# ARM_PCB.net
KiCad netlist of a schematic drawn in Altium Designer
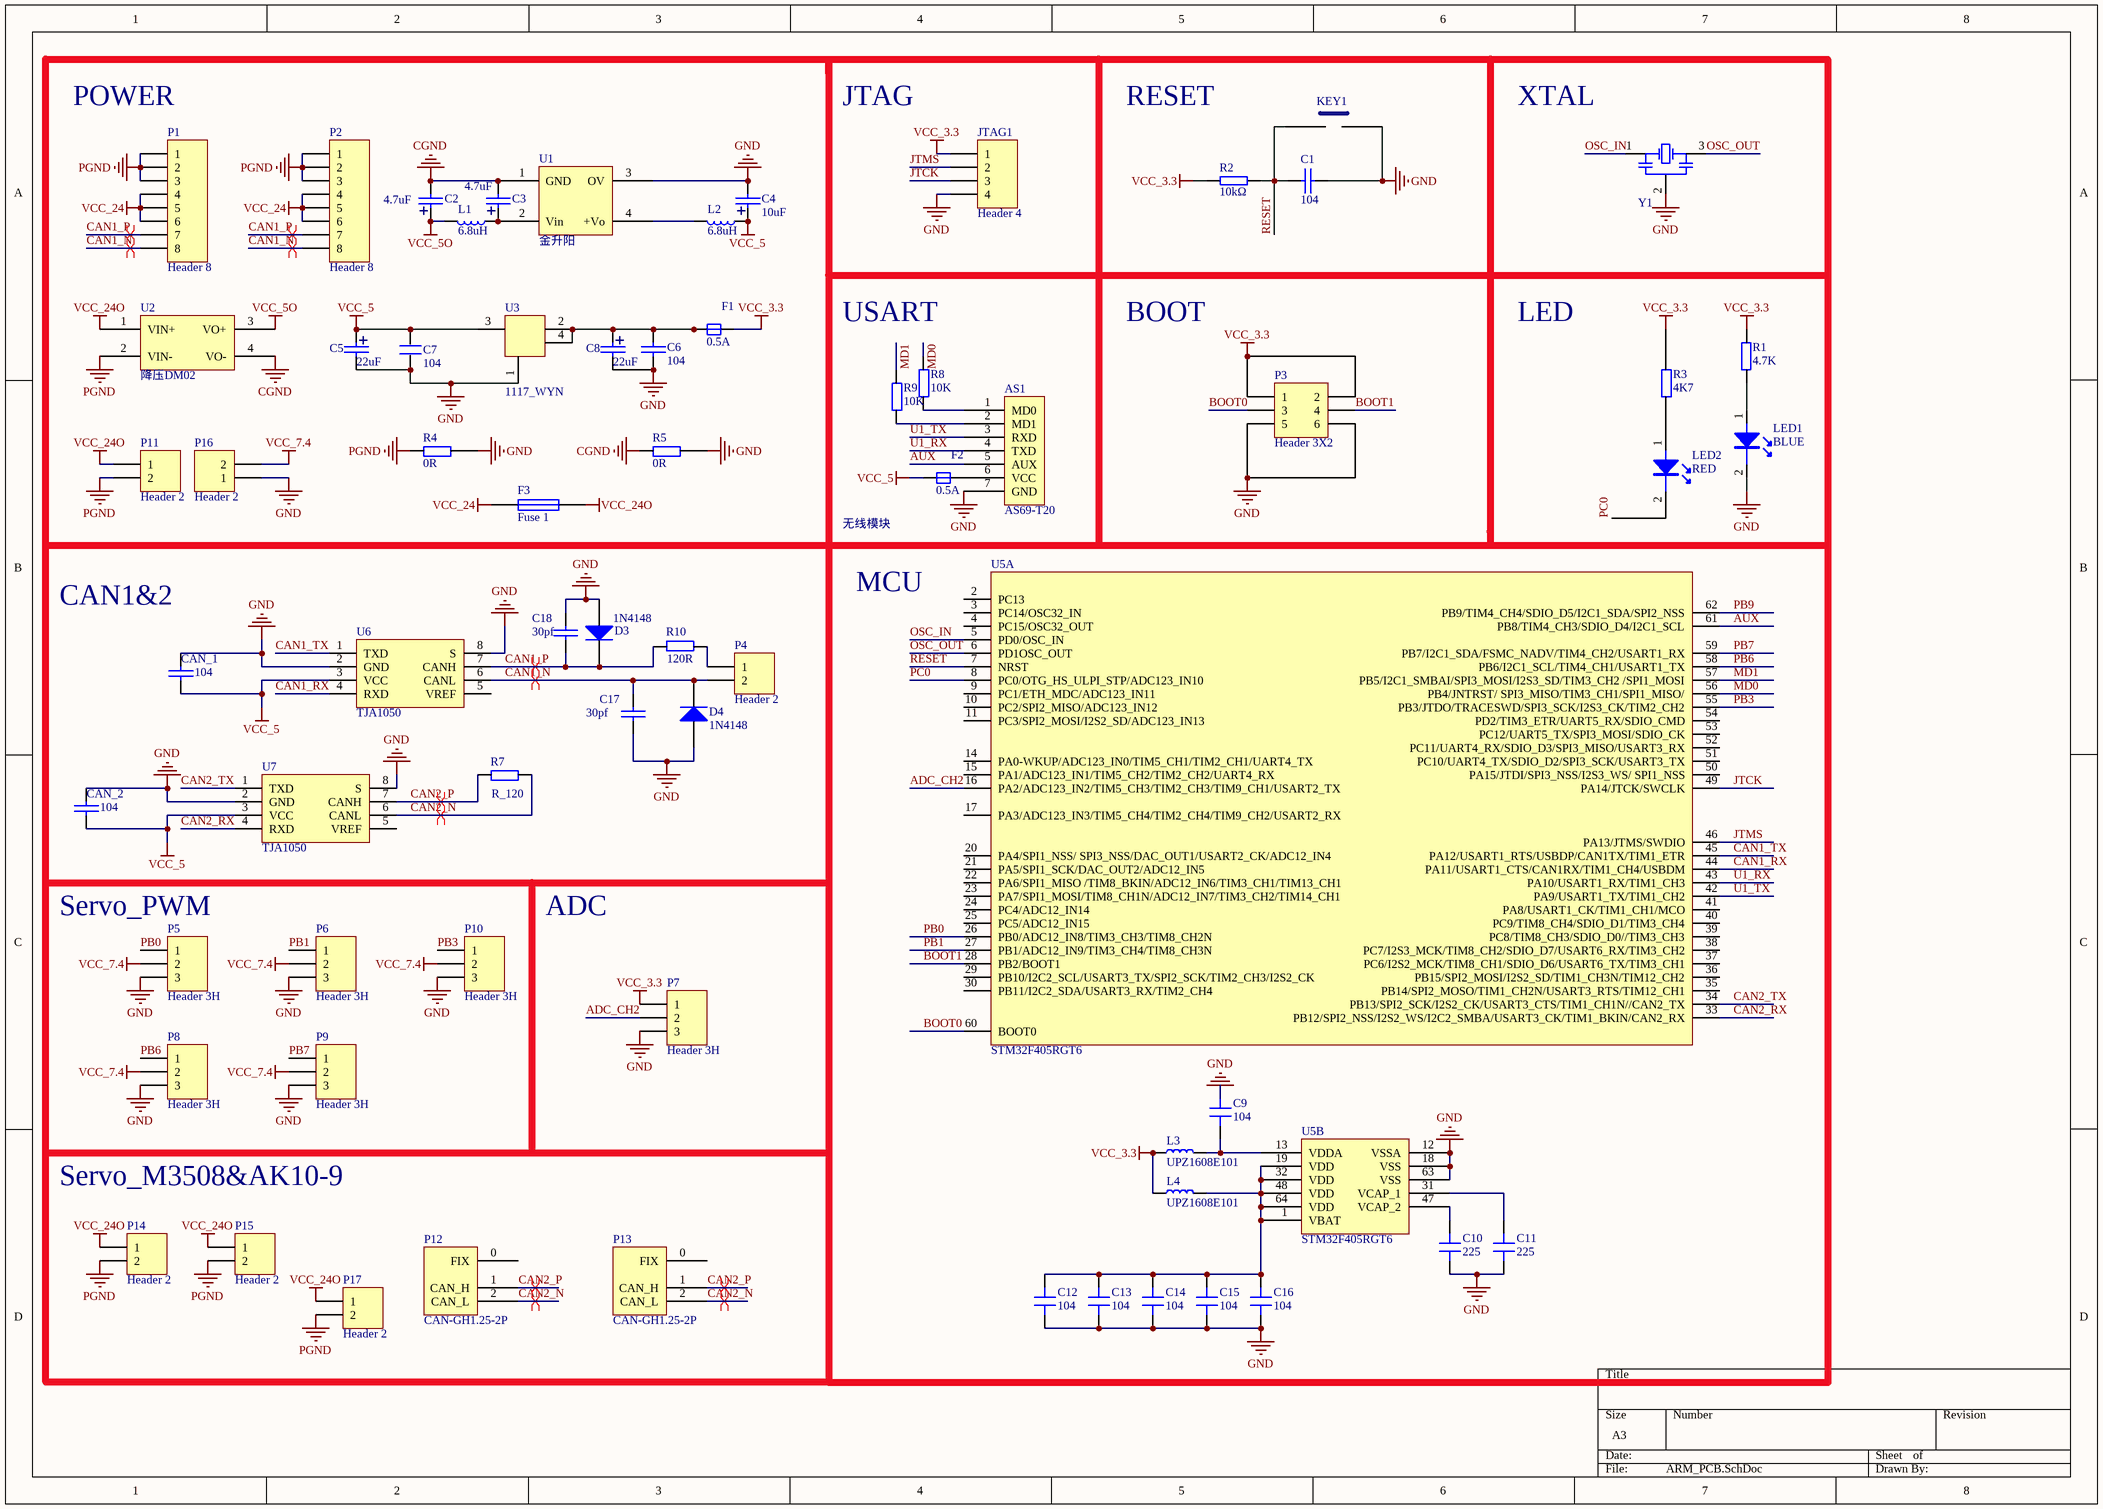
[diagram p0: ARM_PCB.SchDoc]

(export (version "E")
  (design (tool "Eeschema 10.0.6"))
  (components
    (comp (ref "AS1")
      (value "AS69-T20")
      (footprint "HDR2.54-M-LI-7P")
      (libsource (lib "PCB_Project") (part "AS69-T20"))
    )
    (comp (ref "C1") (value "104") (footprint "C0603") (libsource (lib "main") (part "C0603")))
    (comp (ref "C2")
      (value "4.7uF")
      (footprint "A3216")
      (libsource (lib "PCB_PROJECT1") (part "CAP_POL_WYN"))
    )
    (comp (ref "C3")
      (value "4.7uF")
      (footprint "A3216")
      (libsource (lib "PCB_PROJECT1") (part "CAP_POL_WYN"))
    )
    (comp (ref "C4") (value "10uF") (footprint "A3216") (libsource (lib "PCB_PROJECT1") (part "CAP_POL_WYN")))
    (comp (ref "C5") (value "22uF") (footprint "A3216") (libsource (lib "PCB_PROJECT1") (part "CAP_POL_WYN")))
    (comp (ref "C6") (value "104") (footprint "C0603") (libsource (lib "main") (part "C0603")))
    (comp (ref "C7") (value "104") (footprint "C0603") (libsource (lib "Rescue") (part "Cap")))
    (comp (ref "C8") (value "22uF") (footprint "A3216") (libsource (lib "PCB_PROJECT1") (part "CAP_POL_WYN")))
    (comp (ref "C9")
      (value "104")
      (footprint "C0603/1608")
      (description "陶瓷电容")
      (libsource (lib "WMJ2019_Devices") (part "陶瓷电容"))
    )
    (comp (ref "C10")
      (value "225")
      (footprint "C0603/1608")
      (description "陶瓷电容")
      (libsource (lib "WMJ2019_Devices") (part "陶瓷电容"))
    )
    (comp (ref "C11")
      (value "225")
      (footprint "C0603/1608")
      (description "陶瓷电容")
      (libsource (lib "WMJ2019_Devices") (part "陶瓷电容"))
    )
    (comp (ref "C12")
      (value "104")
      (footprint "C0603/1608")
      (description "陶瓷电容")
      (libsource (lib "WMJ2019_Devices") (part "陶瓷电容"))
    )
    (comp (ref "C13")
      (value "104")
      (footprint "C0603/1608")
      (description "陶瓷电容")
      (libsource (lib "WMJ2019_Devices") (part "陶瓷电容"))
    )
    (comp (ref "C14")
      (value "104")
      (footprint "C0603/1608")
      (description "陶瓷电容")
      (libsource (lib "WMJ2019_Devices") (part "陶瓷电容"))
    )
    (comp (ref "C15")
      (value "104")
      (footprint "C0603/1608")
      (description "陶瓷电容")
      (libsource (lib "WMJ2019_Devices") (part "陶瓷电容"))
    )
    (comp (ref "C16")
      (value "104")
      (footprint "C0603/1608")
      (description "陶瓷电容")
      (libsource (lib "WMJ2019_Devices") (part "陶瓷电容"))
    )
    (comp (ref "C17") (value "30pf") (footprint "C0603") (libsource (lib "PCB_Project") (part "CAP_WYN")))
    (comp (ref "C18") (value "30pf") (footprint "C0603") (libsource (lib "PCB_Project") (part "CAP_WYN")))
    (comp (ref "CAN_1") (value "104") (footprint "C0603") (libsource (lib "STM32主处理板") (part "C0603")))
    (comp (ref "CAN_2") (value "104") (footprint "C0603") (libsource (lib "STM32主处理板") (part "C0603")))
    (comp (ref "D3")
      (value "1N4148")
      (footprint "MINI_MELF (LL34)")
      (description "Default Diode")
      (fields (field (name "PUBLISHER") "Altium Limited"))
      (libsource (lib "Miscellaneous Devices") (part "Diode"))
    )
    (comp (ref "D4")
      (value "1N4148")
      (footprint "MINI_MELF (LL34)")
      (description "Default Diode")
      (fields (field (name "PUBLISHER") "Altium Limited"))
      (libsource (lib "Miscellaneous Devices") (part "Diode"))
    )
    (comp (ref "F1") (value "0.5A") (footprint "L0603") (libsource (lib "舞蹈常用原理图库") (part "FUSE")))
    (comp (ref "F2") (value "0.5A") (footprint "L0603") (libsource (lib "舞蹈常用原理图库") (part "FUSE")))
    (comp (ref "F3")
      (value "Fuse 1")
      (footprint "Fuse")
      (description "Fuse")
      (fields (field (name "PUBLISHER") "Altium Limited"))
      (libsource (lib "Miscellaneous Devices") (part "Fuse 1"))
    )
    (comp (ref "JTAG1")
      (value "Header 4")
      (footprint "Header1*4_XH2.54_zhi")
      (description "Header, 4-Pin")
      (fields (field (name "PUBLISHER") "Altium Limited"))
      (libsource (lib "Miscellaneous Connectors") (part "Header 4"))
    )
    (comp (ref "KEY1") (value "KEY2") (footprint "KEY_RESET") (libsource (lib "library-1") (part "KEY")))
    (comp (ref "L1")
      (value "6.8uH")
      (footprint "L0630")
      (description "贴片磁珠")
      (libsource (lib "PCB_Project") (part "磁珠"))
    )
    (comp (ref "L2")
      (value "6.8uH")
      (footprint "L0630")
      (description "贴片磁珠")
      (libsource (lib "PCB_Project") (part "磁珠"))
    )
    (comp (ref "L3")
      (value "UPZ1608E101")
      (footprint "L0603/1608")
      (description "贴片磁珠")
      (libsource (lib "WMJ2019_Devices") (part "磁珠"))
    )
    (comp (ref "L4")
      (value "UPZ1608E101")
      (footprint "L0603/1608")
      (description "贴片磁珠")
      (libsource (lib "WMJ2019_Devices") (part "磁珠"))
    )
    (comp (ref "LED1")
      (value "LED BLUE")
      (footprint "LED0603")
      (fields (field (name "COLOR") "BLUE"))
      (libsource (lib "Rescue") (part "LED"))
    )
    (comp (ref "LED2")
      (value "LED RED")
      (footprint "LED0603")
      (fields (field (name "COLOR") "RED"))
      (libsource (lib "Rescue") (part "LED"))
    )
    (comp (ref "P1")
      (value "Header 8")
      (footprint "XH2.54-WI-8P")
      (description "Header, 8-Pin")
      (fields (field (name "PUBLISHER") "Altium Limited"))
      (libsource (lib "Miscellaneous Connectors") (part "Header 8"))
    )
    (comp (ref "P2")
      (value "Header 8")
      (footprint "Header1*8_XH2.54_zhi")
      (description "Header, 8-Pin")
      (fields (field (name "PUBLISHER") "Altium Limited"))
      (libsource (lib "Miscellaneous Connectors") (part "Header 8"))
    )
    (comp (ref "P3")
      (value "Header 3X2")
      (footprint "BOOT")
      (description "Header, 3-Pin, Dual row")
      (fields (field (name "PUBLISHER") "Altium Limited"))
      (libsource (lib "PCB_Project") (part "Header 3X2"))
    )
    (comp (ref "P4") (value "Header 2") (footprint "TM") (libsource (lib "") (part "Header 2_1")))
    (comp (ref "P5")
      (value "Header 3H")
      (footprint "XH2.54-WI-3P")
      (libsource (lib "Rescue") (part "Header 3H"))
    )
    (comp (ref "P6")
      (value "Header 3H")
      (footprint "XH2.54-WI-3P")
      (libsource (lib "Rescue") (part "Header 3H"))
    )
    (comp (ref "P7")
      (value "Header 3H")
      (footprint "XH2.54-WI-3P")
      (libsource (lib "Rescue") (part "Header 3H"))
    )
    (comp (ref "P8")
      (value "Header 3H")
      (footprint "XH2.54-WI-3P")
      (libsource (lib "Rescue") (part "Header 3H"))
    )
    (comp (ref "P9")
      (value "Header 3H")
      (footprint "XH2.54-WI-3P")
      (libsource (lib "Rescue") (part "Header 3H"))
    )
    (comp (ref "P10")
      (value "Header 3H")
      (footprint "XH2.54-WI-3P")
      (libsource (lib "Rescue") (part "Header 3H"))
    )
    (comp (ref "P11") (value "Header 2") (footprint "KF301-5.0-2P") (libsource (lib "") (part "Header 2_1")))
    (comp (ref "P12")
      (value "CAN-GH1.25-2P")
      (footprint "XH2.54-LI-2P")
      (description "CAN-GH1.25-2P端子座")
      (libsource (lib "PCB_Project1") (part "CAN-GH1.25-2P"))
    )
    (comp (ref "P13")
      (value "CAN-GH1.25-2P")
      (footprint "XH2.54-LI-2P")
      (description "CAN-GH1.25-2P端子座")
      (libsource (lib "PCB_Project1") (part "CAN-GH1.25-2P"))
    )
    (comp (ref "P14") (value "Header 2") (footprint "xt30公头（立式）") (libsource (lib "") (part "Header 2_1")))
    (comp (ref "P15") (value "Header 2") (footprint "xt30公头（立式）") (libsource (lib "") (part "Header 2_1")))
    (comp (ref "P16")
      (value "Header 2")
      (footprint "KF301-5.0-2P")
      (libsource (lib "Rescue") (part "Header 2"))
    )
    (comp (ref "P17") (value "Header 2") (footprint "XT30_母") (libsource (lib "") (part "Header 2_1")))
    (comp (ref "R1") (value "4.7K") (footprint "R0603") (libsource (lib "战舰STM32开发板底板封装库") (part "R")))
    (comp (ref "R2") (value "10kΩ") (footprint "R0603") (libsource (lib "main") (part "RES_WYN")))
    (comp (ref "R3") (value "4K7") (footprint "R0603") (libsource (lib "Rescue") (part "Resistor")))
    (comp (ref "R4") (value "0R") (footprint "R0603") (libsource (lib "Rescue") (part "Resistor")))
    (comp (ref "R5") (value "0R") (footprint "R0603") (libsource (lib "Rescue") (part "Resistor")))
    (comp (ref "R7") (value "R_120") (footprint "R0603") (libsource (lib "战舰STM32开发板底板封装库") (part "R")))
    (comp (ref "R8") (value "10K") (footprint "R0603") (libsource (lib "PCB_Project") (part "Resistor")))
    (comp (ref "R9") (value "10K") (footprint "R0603") (libsource (lib "PCB_Project") (part "Resistor")))
    (comp (ref "R10") (value "120R") (footprint "R0603") (libsource (lib "PCB_Project") (part "Resistor")))
    (comp (ref "U1") (value "金升阳") (footprint "金升阳") (libsource (lib "RESCUE2019") (part "金升阳")))
    (comp (ref "U2") (value "降压DM02") (footprint "降压DM02") (libsource (lib "Rescue") (part "降压DM02")))
    (comp (ref "U3") (value "1117_WYN") (footprint "SOT-223") (libsource (lib "STM32主处理板") (part "1117_WYN")))
    (comp (ref "U5")
      (value "STM32F405RGT6")
      (footprint "LQFP64")
      (description "微控制器STM32F405RGT6")
      (libsource (lib "WMJ2019_MCU") (part "STM32F405RGT6"))
    )
    (comp (ref "U6") (value "TJA1050") (footprint "SO8_M") (libsource (lib "Rescue") (part "TJA1050")))
    (comp (ref "U7") (value "TJA1050") (footprint "SO8_M") (libsource (lib "Rescue") (part "TJA1050")))
    (comp (ref "Y1")
      (value "Crystal_Cap")
      (footprint "XTAL-3213")
      (fields (field (name "PUBLISHER") "Altium Limited"))
      (libsource (lib "chassis_PCB_Project") (part "Crystal_Cap"))
    )
  )
  (nets
    (net (code "1") (name "/ADC_CH2") (class "Default")
      (node (ref "P7") (pin "2") (pinfunction "2_2") (pintype "passive"))
      (node (ref "U5") (pin "16") (pinfunction "PA2/ADC123_IN2/TIM5_CH3/TIM2_CH3/TIM9_CH1/USART2_TX_16") (pintype "passive"))
    )
    (net (code "2") (name "/AUX") (class "Default")
      (node (ref "AS1") (pin "5") (pinfunction "AUX_5") (pintype "passive"))
      (node (ref "U5") (pin "61") (pinfunction "PB8/TIM4_CH3/SDIO_D4/I2C1_SCL_61") (pintype "passive"))
    )
    (net (code "3") (name "/BOOT0") (class "Default")
      (node (ref "P3") (pin "3") (pinfunction "3_3") (pintype "passive"))
      (node (ref "U5") (pin "60") (pinfunction "BOOT0_60") (pintype "passive"))
    )
    (net (code "4") (name "/BOOT1") (class "Default")
      (node (ref "P3") (pin "4") (pinfunction "4_4") (pintype "passive"))
      (node (ref "U5") (pin "28") (pinfunction "PB2/BOOT1_28") (pintype "passive"))
    )
    (net (code "5") (name "/CAN1_N") (class "Default")
      (node (ref "C17") (pin "1") (pintype "passive"))
      (node (ref "D4") (pin "2") (pinfunction "K_2") (pintype "passive"))
      (node (ref "P1") (pin "8") (pinfunction "8_8") (pintype "passive"))
      (node (ref "P2") (pin "8") (pinfunction "8_8") (pintype "passive"))
      (node (ref "P4") (pin "2") (pinfunction "2_2") (pintype "passive"))
      (node (ref "U6") (pin "6") (pinfunction "CANL_6") (pintype "passive"))
    )
    (net (code "6") (name "/CAN1_P") (class "Default")
      (node (ref "C18") (pin "2") (pintype "passive"))
      (node (ref "D3") (pin "2") (pinfunction "K_2") (pintype "passive"))
      (node (ref "P1") (pin "7") (pinfunction "7_7") (pintype "passive"))
      (node (ref "P2") (pin "7") (pinfunction "7_7") (pintype "passive"))
      (node (ref "R10") (pin "2") (pintype "passive"))
      (node (ref "U6") (pin "7") (pinfunction "CANH_7") (pintype "passive"))
    )
    (net (code "7") (name "/CAN1_RX") (class "Default")
      (node (ref "U5") (pin "44") (pinfunction "PA11/USART1_CTS/CAN1RX/TIM1_CH4/USBDM_44") (pintype "passive"))
      (node (ref "U6") (pin "4") (pinfunction "RXD_4") (pintype "passive"))
    )
    (net (code "8") (name "/CAN1_TX") (class "Default")
      (node (ref "U5") (pin "45") (pinfunction "PA12/USART1_RTS/USBDP/CAN1TX/TIM1_ETR_45") (pintype "passive"))
      (node (ref "U6") (pin "1") (pinfunction "TXD_1") (pintype "passive"))
    )
    (net (code "9") (name "/CAN2_N") (class "Default")
      (node (ref "P12") (pin "2") (pinfunction "CAN_L_2") (pintype "passive"))
      (node (ref "P13") (pin "2") (pinfunction "CAN_L_2") (pintype "passive"))
      (node (ref "R7") (pin "2") (pintype "passive"))
      (node (ref "U7") (pin "6") (pinfunction "CANL_6") (pintype "passive"))
    )
    (net (code "10") (name "/CAN2_P") (class "Default")
      (node (ref "P12") (pin "1") (pinfunction "CAN_H_1") (pintype "passive"))
      (node (ref "P13") (pin "1") (pinfunction "CAN_H_1") (pintype "passive"))
      (node (ref "R7") (pin "1") (pintype "passive"))
      (node (ref "U7") (pin "7") (pinfunction "CANH_7") (pintype "passive"))
    )
    (net (code "11") (name "/CAN2_RX") (class "Default")
      (node (ref "U5") (pin "33") (pinfunction "PB12/SPI2_NSS/I2S2_WS/I2C2_SMBA/USART3_CK/TIM1_BKIN/CAN2_RX_33") (pintype "passive"))
      (node (ref "U7") (pin "4") (pinfunction "RXD_4") (pintype "passive"))
    )
    (net (code "12") (name "/CAN2_TX") (class "Default")
      (node (ref "U5") (pin "34") (pinfunction "PB13/SPI2_SCK/I2S2_CK/USART3_CTS/TIM1_CH1N//CAN2_TX_34") (pintype "passive"))
      (node (ref "U7") (pin "1") (pinfunction "TXD_1") (pintype "passive"))
    )
    (net (code "13") (name "/JTCK") (class "Default")
      (node (ref "JTAG1") (pin "3") (pinfunction "3_3") (pintype "passive"))
      (node (ref "U5") (pin "49") (pinfunction "PA14/JTCK/SWCLK_49") (pintype "passive"))
    )
    (net (code "14") (name "/JTMS") (class "Default")
      (node (ref "JTAG1") (pin "2") (pinfunction "2_2") (pintype "passive"))
      (node (ref "U5") (pin "46") (pinfunction "PA13/JTMS/SWDIO_46") (pintype "passive"))
    )
    (net (code "15") (name "/MD0") (class "Default")
      (node (ref "R8") (pin "2") (pintype "passive"))
      (node (ref "U5") (pin "56") (pinfunction "PB4/JNTRST/_SPI3_MISO/TIM3_CH1/SPI1_MISO/_56") (pintype "passive"))
    )
    (net (code "16") (name "/MD1") (class "Default")
      (node (ref "R9") (pin "2") (pintype "passive"))
      (node (ref "U5") (pin "57") (pinfunction "PB5/I2C1_SMBAI/SPI3_MOSI/I2S3_SD/TIM3_CH2_/SPI1_MOSI_57") (pintype "passive"))
    )
    (net (code "17") (name "/OSC_IN") (class "Default")
      (node (ref "U5") (pin "5") (pinfunction "PD0/OSC_IN_5") (pintype "passive"))
      (node (ref "Y1") (pin "1") (pinfunction "OSC1_1") (pintype "passive"))
    )
    (net (code "18") (name "/OSC_OUT") (class "Default")
      (node (ref "U5") (pin "6") (pinfunction "PD1OSC_OUT_6") (pintype "passive"))
      (node (ref "Y1") (pin "3") (pinfunction "OSC3_3") (pintype "passive"))
    )
    (net (code "19") (name "/PB0") (class "Default")
      (node (ref "P5") (pin "1") (pinfunction "1_1") (pintype "passive"))
      (node (ref "U5") (pin "26") (pinfunction "PB0/ADC12_IN8/TIM3_CH3/TIM8_CH2N_26") (pintype "passive"))
    )
    (net (code "20") (name "/PB1") (class "Default")
      (node (ref "P6") (pin "1") (pinfunction "1_1") (pintype "passive"))
      (node (ref "U5") (pin "27") (pinfunction "PB1/ADC12_IN9/TIM3_CH4/TIM8_CH3N_27") (pintype "passive"))
    )
    (net (code "21") (name "/PB3") (class "Default")
      (node (ref "P10") (pin "1") (pinfunction "1_1") (pintype "passive"))
      (node (ref "U5") (pin "55") (pinfunction "PB3/JTDO/TRACESWD/SPI3_SCK/I2S3_CK/TIM2_CH2_55") (pintype "passive"))
    )
    (net (code "22") (name "/PB6") (class "Default")
      (node (ref "P8") (pin "1") (pinfunction "1_1") (pintype "passive"))
      (node (ref "U5") (pin "58") (pinfunction "PB6/I2C1_SCL/TIM4_CH1/USART1_TX_58") (pintype "passive"))
    )
    (net (code "23") (name "/PB7") (class "Default")
      (node (ref "P9") (pin "1") (pinfunction "1_1") (pintype "passive"))
      (node (ref "U5") (pin "59") (pinfunction "PB7/I2C1_SDA/FSMC_NADV/TIM4_CH2/USART1_RX_59") (pintype "passive"))
    )
    (net (code "24") (name "/PB9") (class "Default")
      (node (ref "U5") (pin "62") (pinfunction "PB9/TIM4_CH4/SDIO_D5/I2C1_SDA/SPI2_NSS_62") (pintype "passive"))
    )
    (net (code "25") (name "/PC0") (class "Default")
      (node (ref "LED2") (pin "2") (pinfunction "K_2") (pintype "passive"))
      (node (ref "U5") (pin "8") (pinfunction "PC0/OTG_HS_ULPI_STP/ADC123_IN10_8") (pintype "passive"))
    )
    (net (code "26") (name "/RESET") (class "Default")
      (node (ref "C1") (pin "1") (pintype "passive"))
      (node (ref "KEY1") (pin "2") (pinfunction "2_2") (pintype "passive"))
      (node (ref "R2") (pin "1") (pinfunction "1_1") (pintype "passive"))
      (node (ref "U5") (pin "7") (pinfunction "NRST_7") (pintype "passive"))
    )
    (net (code "27") (name "/U1_RX") (class "Default")
      (node (ref "AS1") (pin "4") (pinfunction "TXD_4") (pintype "passive"))
      (node (ref "U5") (pin "43") (pinfunction "PA10/USART1_RX/TIM1_CH3_43") (pintype "passive"))
    )
    (net (code "28") (name "/U1_TX") (class "Default")
      (node (ref "AS1") (pin "3") (pinfunction "RXD_3") (pintype "passive"))
      (node (ref "U5") (pin "42") (pinfunction "PA9/USART1_TX/TIM1_CH2_42") (pintype "passive"))
    )
    (net (code "29") (name "CGND") (class "Default")
      (node (ref "C2") (pin "2") (pintype "passive"))
      (node (ref "C3") (pin "2") (pintype "passive"))
      (node (ref "R5") (pin "1") (pintype "passive"))
      (node (ref "U1") (pin "1") (pinfunction "GND_1") (pintype "passive"))
      (node (ref "U2") (pin "4") (pinfunction "VO-_4") (pintype "passive"))
    )
    (net (code "30") (name "GND") (class "Default")
      (node (ref "AS1") (pin "7") (pinfunction "GND_7") (pintype "passive"))
      (node (ref "C1") (pin "2") (pintype "passive"))
      (node (ref "C10") (pin "1") (pintype "passive"))
      (node (ref "C11") (pin "1") (pintype "passive"))
      (node (ref "C12") (pin "1") (pintype "passive"))
      (node (ref "C13") (pin "1") (pintype "passive"))
      (node (ref "C14") (pin "1") (pintype "passive"))
      (node (ref "C15") (pin "1") (pintype "passive"))
      (node (ref "C16") (pin "1") (pintype "passive"))
      (node (ref "C17") (pin "2") (pintype "passive"))
      (node (ref "C18") (pin "1") (pintype "passive"))
      (node (ref "C4") (pin "2") (pintype "passive"))
      (node (ref "C5") (pin "2") (pintype "passive"))
      (node (ref "C6") (pin "2") (pintype "passive"))
      (node (ref "C7") (pin "1") (pintype "passive"))
      (node (ref "C8") (pin "2") (pintype "passive"))
      (node (ref "C9") (pin "2") (pintype "passive"))
      (node (ref "CAN_1") (pin "1") (pintype "passive"))
      (node (ref "CAN_2") (pin "1") (pintype "passive"))
      (node (ref "D3") (pin "1") (pinfunction "A_1") (pintype "passive"))
      (node (ref "D4") (pin "1") (pinfunction "A_1") (pintype "passive"))
      (node (ref "JTAG1") (pin "4") (pinfunction "4_4") (pintype "passive"))
      (node (ref "KEY1") (pin "1") (pinfunction "1_1") (pintype "passive"))
      (node (ref "LED1") (pin "2") (pinfunction "K_2") (pintype "passive"))
      (node (ref "P10") (pin "3") (pinfunction "3_3") (pintype "passive"))
      (node (ref "P16") (pin "1") (pinfunction "1_1") (pintype "passive"))
      (node (ref "P3") (pin "5") (pinfunction "5_5") (pintype "passive"))
      (node (ref "P3") (pin "6") (pinfunction "6_6") (pintype "passive"))
      (node (ref "P5") (pin "3") (pinfunction "3_3") (pintype "passive"))
      (node (ref "P6") (pin "3") (pinfunction "3_3") (pintype "passive"))
      (node (ref "P7") (pin "3") (pinfunction "3_3") (pintype "passive"))
      (node (ref "P8") (pin "3") (pinfunction "3_3") (pintype "passive"))
      (node (ref "P9") (pin "3") (pinfunction "3_3") (pintype "passive"))
      (node (ref "R4") (pin "2") (pintype "passive"))
      (node (ref "R5") (pin "2") (pintype "passive"))
      (node (ref "U1") (pin "3") (pinfunction "OV_3") (pintype "passive"))
      (node (ref "U3") (pin "1") (pintype "passive"))
      (node (ref "U5") (pin "12") (pinfunction "VSSA_12") (pintype "passive"))
      (node (ref "U5") (pin "18") (pinfunction "VSS_18") (pintype "passive"))
      (node (ref "U5") (pin "63") (pinfunction "VSS_63") (pintype "passive"))
      (node (ref "U6") (pin "2") (pinfunction "GND_2") (pintype "passive"))
      (node (ref "U6") (pin "8") (pinfunction "S_8") (pintype "passive"))
      (node (ref "U7") (pin "2") (pinfunction "GND_2") (pintype "passive"))
      (node (ref "U7") (pin "8") (pinfunction "S_8") (pintype "passive"))
      (node (ref "Y1") (pin "2") (pinfunction "OSC2_2") (pintype "passive"))
    )
    (net (code "31") (name "Net-(AS1-MD0)") (class "Default")
      (node (ref "AS1") (pin "1") (pinfunction "MD0_1") (pintype "passive"))
      (node (ref "R8") (pin "1") (pintype "passive"))
    )
    (net (code "32") (name "Net-(AS1-MD1)") (class "Default")
      (node (ref "AS1") (pin "2") (pinfunction "MD1_2") (pintype "passive"))
      (node (ref "R9") (pin "1") (pintype "passive"))
    )
    (net (code "33") (name "Net-(AS1-VCC)") (class "Default")
      (node (ref "AS1") (pin "6") (pinfunction "VCC_6") (pintype "passive"))
      (node (ref "F2") (pin "2") (pintype "passive"))
    )
    (net (code "34") (name "Net-(C6-Pad1)") (class "Default")
      (node (ref "C6") (pin "1") (pintype "passive"))
      (node (ref "C8") (pin "1") (pintype "passive"))
      (node (ref "F1") (pin "1") (pintype "passive"))
      (node (ref "U3") (pin "2") (pintype "passive"))
      (node (ref "U3") (pin "4") (pintype "passive"))
    )
    (net (code "35") (name "Net-(LED1-A)") (class "Default")
      (node (ref "LED1") (pin "1") (pinfunction "A_1") (pintype "passive"))
      (node (ref "R1") (pin "2") (pintype "passive"))
    )
    (net (code "36") (name "Net-(LED2-A)") (class "Default")
      (node (ref "LED2") (pin "1") (pinfunction "A_1") (pintype "passive"))
      (node (ref "R3") (pin "1") (pintype "passive"))
    )
    (net (code "37") (name "Net-(P4-Pad1)") (class "Default")
      (node (ref "P4") (pin "1") (pinfunction "1_1") (pintype "passive"))
      (node (ref "R10") (pin "1") (pintype "passive"))
    )
    (net (code "38") (name "Net-(U1-+Vo)") (class "Default")
      (node (ref "L2") (pin "2") (pinfunction "2_2") (pintype "passive"))
      (node (ref "U1") (pin "4") (pinfunction "+Vo_4") (pintype "passive"))
    )
    (net (code "39") (name "Net-(U1-Vin)") (class "Default")
      (node (ref "C3") (pin "1") (pintype "passive"))
      (node (ref "L1") (pin "1") (pinfunction "1_1") (pintype "passive"))
      (node (ref "U1") (pin "2") (pinfunction "Vin_2") (pintype "passive"))
    )
    (net (code "40") (name "Net-(U5B-VBAT)") (class "Default")
      (node (ref "C12") (pin "2") (pintype "passive"))
      (node (ref "C13") (pin "2") (pintype "passive"))
      (node (ref "C14") (pin "2") (pintype "passive"))
      (node (ref "C15") (pin "2") (pintype "passive"))
      (node (ref "C16") (pin "2") (pintype "passive"))
      (node (ref "L4") (pin "2") (pinfunction "2_2") (pintype "passive"))
      (node (ref "U5") (pin "1") (pinfunction "VBAT_1") (pintype "passive"))
      (node (ref "U5") (pin "19") (pinfunction "VDD_19") (pintype "passive"))
      (node (ref "U5") (pin "32") (pinfunction "VDD_32") (pintype "passive"))
      (node (ref "U5") (pin "48") (pinfunction "VDD_48") (pintype "passive"))
      (node (ref "U5") (pin "64") (pinfunction "VDD_64") (pintype "passive"))
    )
    (net (code "41") (name "Net-(U5B-VCAP_1)") (class "Default")
      (node (ref "C11") (pin "2") (pintype "passive"))
      (node (ref "U5") (pin "31") (pinfunction "VCAP_1_31") (pintype "passive"))
    )
    (net (code "42") (name "Net-(U5B-VCAP_2)") (class "Default")
      (node (ref "C10") (pin "2") (pintype "passive"))
      (node (ref "U5") (pin "47") (pinfunction "VCAP_2_47") (pintype "passive"))
    )
    (net (code "43") (name "Net-(U5B-VDDA)") (class "Default")
      (node (ref "C9") (pin "1") (pintype "passive"))
      (node (ref "L3") (pin "2") (pinfunction "2_2") (pintype "passive"))
      (node (ref "U5") (pin "13") (pinfunction "VDDA_13") (pintype "passive"))
    )
    (net (code "44") (name "PGND") (class "Default")
      (node (ref "P1") (pin "1") (pinfunction "1_1") (pintype "passive"))
      (node (ref "P1") (pin "2") (pinfunction "2_2") (pintype "passive"))
      (node (ref "P1") (pin "3") (pinfunction "3_3") (pintype "passive"))
      (node (ref "P11") (pin "2") (pinfunction "2_2") (pintype "passive"))
      (node (ref "P14") (pin "2") (pinfunction "2_2") (pintype "passive"))
      (node (ref "P15") (pin "2") (pinfunction "2_2") (pintype "passive"))
      (node (ref "P17") (pin "2") (pinfunction "2_2") (pintype "passive"))
      (node (ref "P2") (pin "1") (pinfunction "1_1") (pintype "passive"))
      (node (ref "P2") (pin "2") (pinfunction "2_2") (pintype "passive"))
      (node (ref "P2") (pin "3") (pinfunction "3_3") (pintype "passive"))
      (node (ref "R4") (pin "1") (pintype "passive"))
      (node (ref "U2") (pin "2") (pinfunction "VIN-_2") (pintype "passive"))
    )
    (net (code "45") (name "VCC_3.3") (class "Default")
      (node (ref "F1") (pin "2") (pintype "passive"))
      (node (ref "JTAG1") (pin "1") (pinfunction "1_1") (pintype "passive"))
      (node (ref "L3") (pin "1") (pinfunction "1_1") (pintype "passive"))
      (node (ref "L4") (pin "1") (pinfunction "1_1") (pintype "passive"))
      (node (ref "P3") (pin "1") (pinfunction "1_1") (pintype "passive"))
      (node (ref "P3") (pin "2") (pinfunction "2_2") (pintype "passive"))
      (node (ref "P7") (pin "1") (pinfunction "1_1") (pintype "passive"))
      (node (ref "R1") (pin "1") (pintype "passive"))
      (node (ref "R2") (pin "2") (pinfunction "2_2") (pintype "passive"))
      (node (ref "R3") (pin "2") (pintype "passive"))
    )
    (net (code "46") (name "VCC_5") (class "Default")
      (node (ref "C4") (pin "1") (pintype "passive"))
      (node (ref "C5") (pin "1") (pintype "passive"))
      (node (ref "C7") (pin "2") (pintype "passive"))
      (node (ref "CAN_1") (pin "2") (pintype "passive"))
      (node (ref "CAN_2") (pin "2") (pintype "passive"))
      (node (ref "F2") (pin "1") (pintype "passive"))
      (node (ref "L2") (pin "1") (pinfunction "1_1") (pintype "passive"))
      (node (ref "U3") (pin "3") (pintype "passive"))
      (node (ref "U6") (pin "3") (pinfunction "VCC_3") (pintype "passive"))
      (node (ref "U7") (pin "3") (pinfunction "VCC_3") (pintype "passive"))
    )
    (net (code "47") (name "VCC_5O") (class "Default")
      (node (ref "C2") (pin "1") (pintype "passive"))
      (node (ref "L1") (pin "2") (pinfunction "2_2") (pintype "passive"))
      (node (ref "U2") (pin "3") (pinfunction "VO+_3") (pintype "passive"))
    )
    (net (code "48") (name "VCC_7.4") (class "Default")
      (node (ref "P10") (pin "2") (pinfunction "2_2") (pintype "passive"))
      (node (ref "P16") (pin "2") (pinfunction "2_2") (pintype "passive"))
      (node (ref "P5") (pin "2") (pinfunction "2_2") (pintype "passive"))
      (node (ref "P6") (pin "2") (pinfunction "2_2") (pintype "passive"))
      (node (ref "P8") (pin "2") (pinfunction "2_2") (pintype "passive"))
      (node (ref "P9") (pin "2") (pinfunction "2_2") (pintype "passive"))
    )
    (net (code "49") (name "VCC_24") (class "Default")
      (node (ref "F3") (pin "1") (pinfunction "1_1") (pintype "passive"))
      (node (ref "P1") (pin "4") (pinfunction "4_4") (pintype "passive"))
      (node (ref "P1") (pin "5") (pinfunction "5_5") (pintype "passive"))
      (node (ref "P1") (pin "6") (pinfunction "6_6") (pintype "passive"))
      (node (ref "P2") (pin "4") (pinfunction "4_4") (pintype "passive"))
      (node (ref "P2") (pin "5") (pinfunction "5_5") (pintype "passive"))
      (node (ref "P2") (pin "6") (pinfunction "6_6") (pintype "passive"))
    )
    (net (code "50") (name "VCC_24O") (class "Default")
      (node (ref "F3") (pin "2") (pinfunction "2_2") (pintype "passive"))
      (node (ref "P11") (pin "1") (pinfunction "1_1") (pintype "passive"))
      (node (ref "P14") (pin "1") (pinfunction "1_1") (pintype "passive"))
      (node (ref "P15") (pin "1") (pinfunction "1_1") (pintype "passive"))
      (node (ref "P17") (pin "1") (pinfunction "1_1") (pintype "passive"))
      (node (ref "U2") (pin "1") (pinfunction "VIN+_1") (pintype "passive"))
    )
    (net (code "51") (name "unconnected-(P12-FIX-Pad0)") (class "Default")
      (node (ref "P12") (pin "0") (pinfunction "FIX_0") (pintype "passive"))
    )
    (net (code "52") (name "unconnected-(P13-FIX-Pad0)") (class "Default")
      (node (ref "P13") (pin "0") (pinfunction "FIX_0") (pintype "passive"))
    )
    (net (code "53") (name "unconnected-(U5A-PA0-WKUP{slash}ADC123_IN0{slash}TIM5_CH1{slash}TIM2_CH1{slash}UART4_TX-Pad14)") (class "Default")
      (node (ref "U5") (pin "14") (pinfunction "PA0-WKUP/ADC123_IN0/TIM5_CH1/TIM2_CH1/UART4_TX_14") (pintype "passive"))
    )
    (net (code "54") (name "unconnected-(U5A-PA1{slash}ADC123_IN1{slash}TIM5_CH2{slash}TIM2_CH2{slash}UART4_RX-Pad15)") (class "Default")
      (node (ref "U5") (pin "15") (pinfunction "PA1/ADC123_IN1/TIM5_CH2/TIM2_CH2/UART4_RX_15") (pintype "passive"))
    )
    (net (code "55") (name "unconnected-(U5A-PA3{slash}ADC123_IN3{slash}TIM5_CH4{slash}TIM2_CH4{slash}TIM9_CH2{slash}USART2_RX-Pad17)") (class "Default")
      (node (ref "U5") (pin "17") (pinfunction "PA3/ADC123_IN3/TIM5_CH4/TIM2_CH4/TIM9_CH2/USART2_RX_17") (pintype "passive"))
    )
    (net (code "56") (name "unconnected-(U5A-PA4{slash}SPI1_NSS{slash}_SPI3_NSS{slash}DAC_OUT1{slash}USART2_CK{slash}ADC12_IN4-Pad20)") (class "Default")
      (node (ref "U5") (pin "20") (pinfunction "PA4/SPI1_NSS/_SPI3_NSS/DAC_OUT1/USART2_CK/ADC12_IN4_20") (pintype "passive"))
    )
    (net (code "57") (name "unconnected-(U5A-PA5{slash}SPI1_SCK{slash}DAC_OUT2{slash}ADC12_IN5-Pad21)") (class "Default")
      (node (ref "U5") (pin "21") (pinfunction "PA5/SPI1_SCK/DAC_OUT2/ADC12_IN5_21") (pintype "passive"))
    )
    (net (code "58") (name "unconnected-(U5A-PA6{slash}SPI1_MISO_{slash}TIM8_BKIN{slash}ADC12_IN6{slash}TIM3_CH1{slash}TIM13_CH1-Pad22)") (class "Default")
      (node (ref "U5") (pin "22") (pinfunction "PA6/SPI1_MISO_/TIM8_BKIN/ADC12_IN6/TIM3_CH1/TIM13_CH1_22") (pintype "passive"))
    )
    (net (code "59") (name "unconnected-(U5A-PA7{slash}SPI1_MOSI{slash}TIM8_CH1N{slash}ADC12_IN7{slash}TIM3_CH2{slash}TIM14_CH1-Pad23)") (class "Default")
      (node (ref "U5") (pin "23") (pinfunction "PA7/SPI1_MOSI/TIM8_CH1N/ADC12_IN7/TIM3_CH2/TIM14_CH1_23") (pintype "passive"))
    )
    (net (code "60") (name "unconnected-(U5A-PA8{slash}USART1_CK{slash}TIM1_CH1{slash}MCO-Pad41)") (class "Default")
      (node (ref "U5") (pin "41") (pinfunction "PA8/USART1_CK/TIM1_CH1/MCO_41") (pintype "passive"))
    )
    (net (code "61") (name "unconnected-(U5A-PA15{slash}JTDI{slash}SPI3_NSS{slash}I2S3_WS{slash}_SPI1_NSS-Pad50)") (class "Default")
      (node (ref "U5") (pin "50") (pinfunction "PA15/JTDI/SPI3_NSS/I2S3_WS/_SPI1_NSS_50") (pintype "passive"))
    )
    (net (code "62") (name "unconnected-(U5A-PB10{slash}I2C2_SCL{slash}USART3_TX{slash}SPI2_SCK{slash}TIM2_CH3{slash}I2S2_CK-Pad29)") (class "Default")
      (node (ref "U5") (pin "29") (pinfunction "PB10/I2C2_SCL/USART3_TX/SPI2_SCK/TIM2_CH3/I2S2_CK_29") (pintype "passive"))
    )
    (net (code "63") (name "unconnected-(U5A-PB11{slash}I2C2_SDA{slash}USART3_RX{slash}TIM2_CH4-Pad30)") (class "Default")
      (node (ref "U5") (pin "30") (pinfunction "PB11/I2C2_SDA/USART3_RX/TIM2_CH4_30") (pintype "passive"))
    )
    (net (code "64") (name "unconnected-(U5A-PB14{slash}SPI2_MOSO{slash}TIM1_CH2N{slash}USART3_RTS{slash}TIM12_CH1-Pad35)") (class "Default")
      (node (ref "U5") (pin "35") (pinfunction "PB14/SPI2_MOSO/TIM1_CH2N/USART3_RTS/TIM12_CH1_35") (pintype "passive"))
    )
    (net (code "65") (name "unconnected-(U5A-PB15{slash}SPI2_MOSI{slash}I2S2_SD{slash}TIM1_CH3N{slash}TIM12_CH2-Pad36)") (class "Default")
      (node (ref "U5") (pin "36") (pinfunction "PB15/SPI2_MOSI/I2S2_SD/TIM1_CH3N/TIM12_CH2_36") (pintype "passive"))
    )
    (net (code "66") (name "unconnected-(U5A-PC1{slash}ETH_MDC{slash}ADC123_IN11-Pad9)") (class "Default")
      (node (ref "U5") (pin "9") (pinfunction "PC1/ETH_MDC/ADC123_IN11_9") (pintype "passive"))
    )
    (net (code "67") (name "unconnected-(U5A-PC2{slash}SPI2_MISO{slash}ADC123_IN12-Pad10)") (class "Default")
      (node (ref "U5") (pin "10") (pinfunction "PC2/SPI2_MISO/ADC123_IN12_10") (pintype "passive"))
    )
    (net (code "68") (name "unconnected-(U5A-PC3{slash}SPI2_MOSI{slash}I2S2_SD{slash}ADC123_IN13-Pad11)") (class "Default")
      (node (ref "U5") (pin "11") (pinfunction "PC3/SPI2_MOSI/I2S2_SD/ADC123_IN13_11") (pintype "passive"))
    )
    (net (code "69") (name "unconnected-(U5A-PC4{slash}ADC12_IN14-Pad24)") (class "Default")
      (node (ref "U5") (pin "24") (pinfunction "PC4/ADC12_IN14_24") (pintype "passive"))
    )
    (net (code "70") (name "unconnected-(U5A-PC5{slash}ADC12_IN15-Pad25)") (class "Default")
      (node (ref "U5") (pin "25") (pinfunction "PC5/ADC12_IN15_25") (pintype "passive"))
    )
    (net (code "71") (name "unconnected-(U5A-PC6{slash}I2S2_MCK{slash}TIM8_CH1{slash}SDIO_D6{slash}USART6_TX{slash}TIM3_CH1-Pad37)") (class "Default")
      (node (ref "U5") (pin "37") (pinfunction "PC6/I2S2_MCK/TIM8_CH1/SDIO_D6/USART6_TX/TIM3_CH1_37") (pintype "passive"))
    )
    (net (code "72") (name "unconnected-(U5A-PC7{slash}I2S3_MCK{slash}TIM8_CH2{slash}SDIO_D7{slash}USART6_RX{slash}TIM3_CH2-Pad38)") (class "Default")
      (node (ref "U5") (pin "38") (pinfunction "PC7/I2S3_MCK/TIM8_CH2/SDIO_D7/USART6_RX/TIM3_CH2_38") (pintype "passive"))
    )
    (net (code "73") (name "unconnected-(U5A-PC8{slash}TIM8_CH3{slash}SDIO_D0{slash}{slash}TIM3_CH3-Pad39)") (class "Default")
      (node (ref "U5") (pin "39") (pinfunction "PC8/TIM8_CH3/SDIO_D0//TIM3_CH3_39") (pintype "passive"))
    )
    (net (code "74") (name "unconnected-(U5A-PC9{slash}TIM8_CH4{slash}SDIO_D1{slash}TIM3_CH4-Pad40)") (class "Default")
      (node (ref "U5") (pin "40") (pinfunction "PC9/TIM8_CH4/SDIO_D1/TIM3_CH4_40") (pintype "passive"))
    )
    (net (code "75") (name "unconnected-(U5A-PC10{slash}UART4_TX{slash}SDIO_D2{slash}SPI3_SCK{slash}USART3_TX-Pad51)") (class "Default")
      (node (ref "U5") (pin "51") (pinfunction "PC10/UART4_TX/SDIO_D2/SPI3_SCK/USART3_TX_51") (pintype "passive"))
    )
    (net (code "76") (name "unconnected-(U5A-PC11{slash}UART4_RX{slash}SDIO_D3{slash}SPI3_MISO{slash}USART3_RX-Pad52)") (class "Default")
      (node (ref "U5") (pin "52") (pinfunction "PC11/UART4_RX/SDIO_D3/SPI3_MISO/USART3_RX_52") (pintype "passive"))
    )
    (net (code "77") (name "unconnected-(U5A-PC12{slash}UART5_TX{slash}SPI3_MOSI{slash}SDIO_CK-Pad53)") (class "Default")
      (node (ref "U5") (pin "53") (pinfunction "PC12/UART5_TX/SPI3_MOSI/SDIO_CK_53") (pintype "passive"))
    )
    (net (code "78") (name "unconnected-(U5A-PC13-Pad2)") (class "Default")
      (node (ref "U5") (pin "2") (pinfunction "PC13_2") (pintype "passive"))
    )
    (net (code "79") (name "unconnected-(U5A-PC14{slash}OSC32_IN-Pad3)") (class "Default")
      (node (ref "U5") (pin "3") (pinfunction "PC14/OSC32_IN_3") (pintype "passive"))
    )
    (net (code "80") (name "unconnected-(U5A-PC15{slash}OSC32_OUT-Pad4)") (class "Default")
      (node (ref "U5") (pin "4") (pinfunction "PC15/OSC32_OUT_4") (pintype "passive"))
    )
    (net (code "81") (name "unconnected-(U5A-PD2{slash}TIM3_ETR{slash}UART5_RX{slash}SDIO_CMD-Pad54)") (class "Default")
      (node (ref "U5") (pin "54") (pinfunction "PD2/TIM3_ETR/UART5_RX/SDIO_CMD_54") (pintype "passive"))
    )
    (net (code "82") (name "unconnected-(U6-VREF-Pad5)") (class "Default")
      (node (ref "U6") (pin "5") (pinfunction "VREF_5") (pintype "passive"))
    )
    (net (code "83") (name "unconnected-(U7-VREF-Pad5)") (class "Default")
      (node (ref "U7") (pin "5") (pinfunction "VREF_5") (pintype "passive"))
    )
  )
)
